# hacker-house-esp32-board.net
KiCad netlist of a schematic drawn in EAGLE
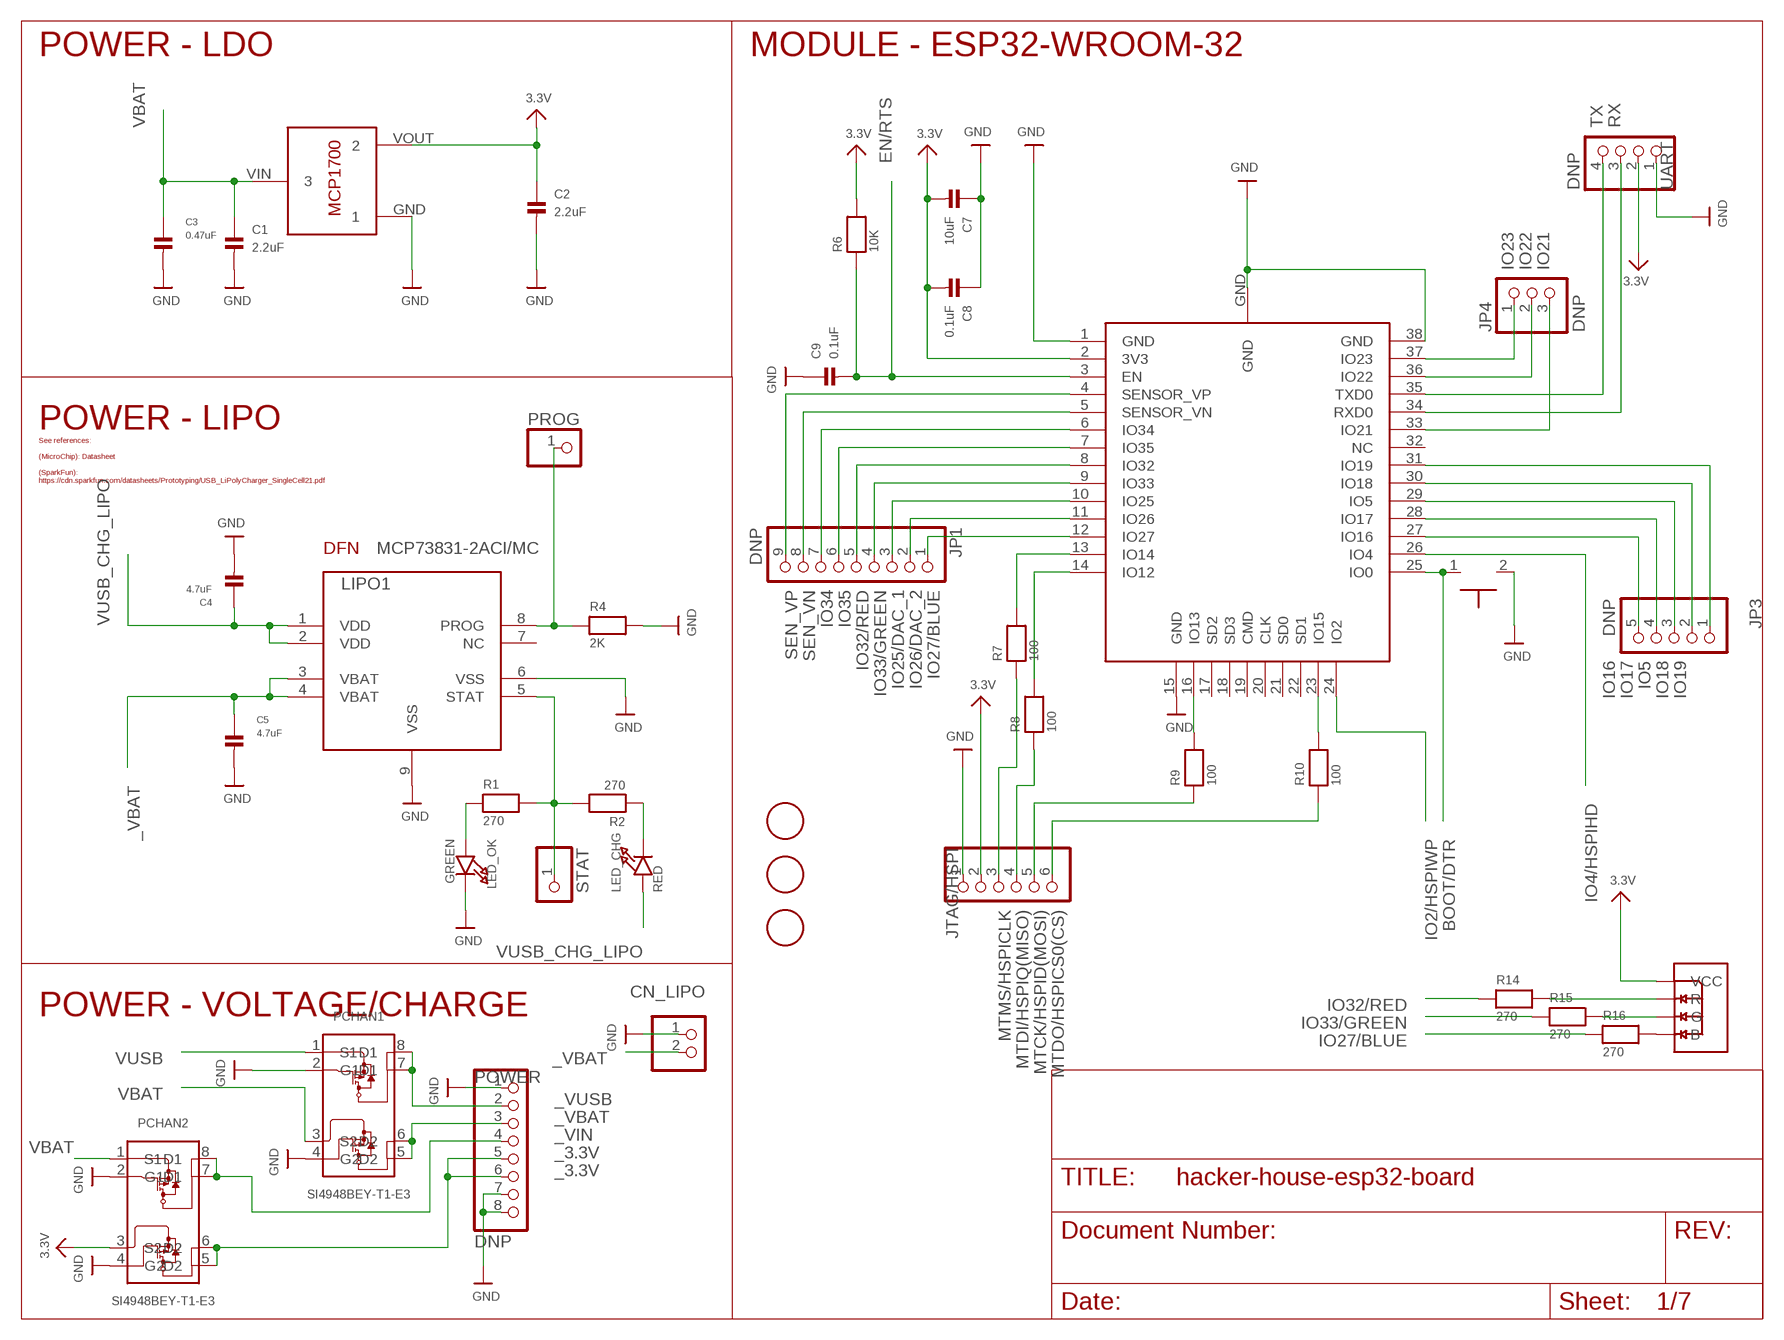
[diagram p0: schematic, sheet 1]
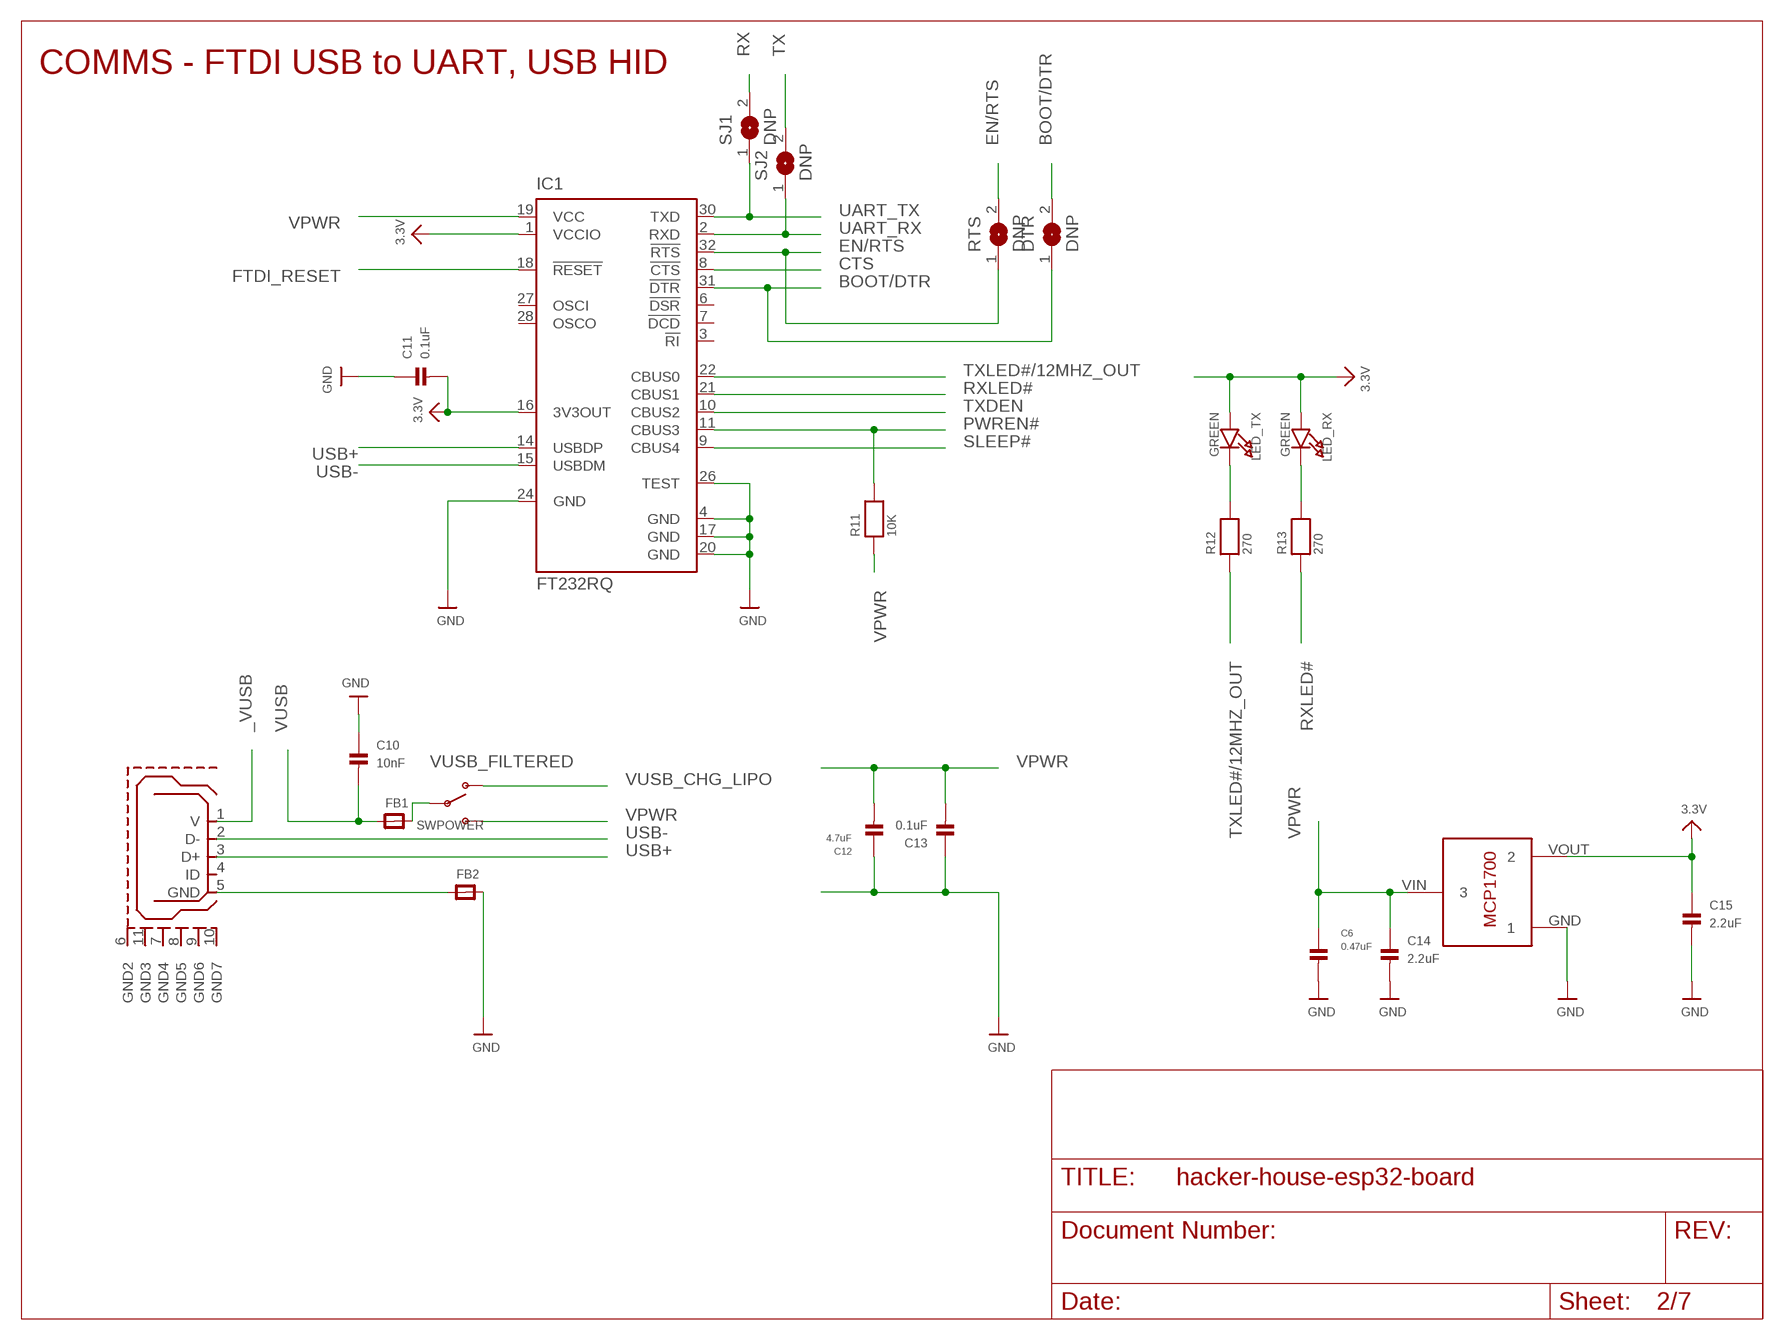
[diagram p1: schematic, sheet 2]
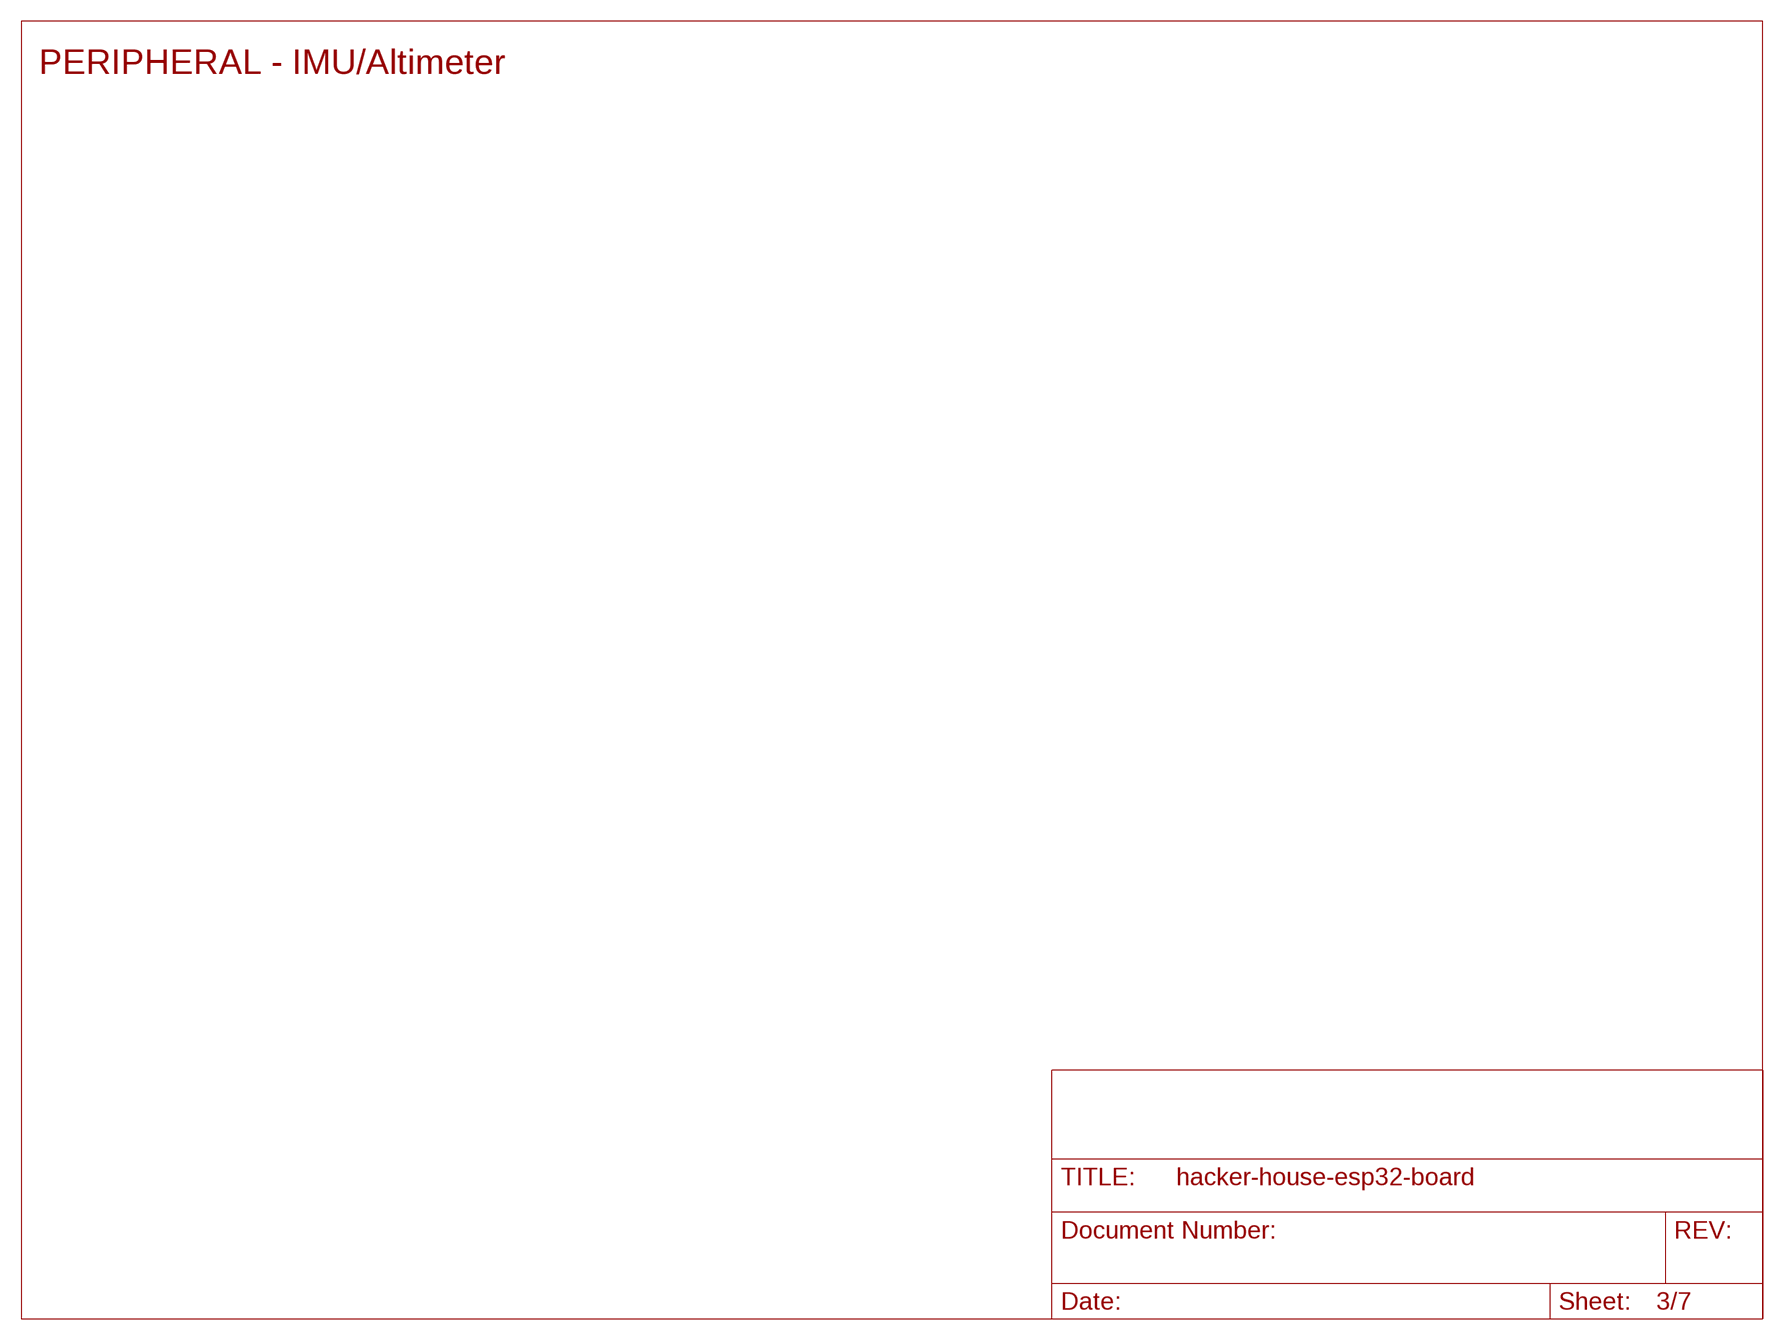
[diagram p2: schematic, sheet 3]
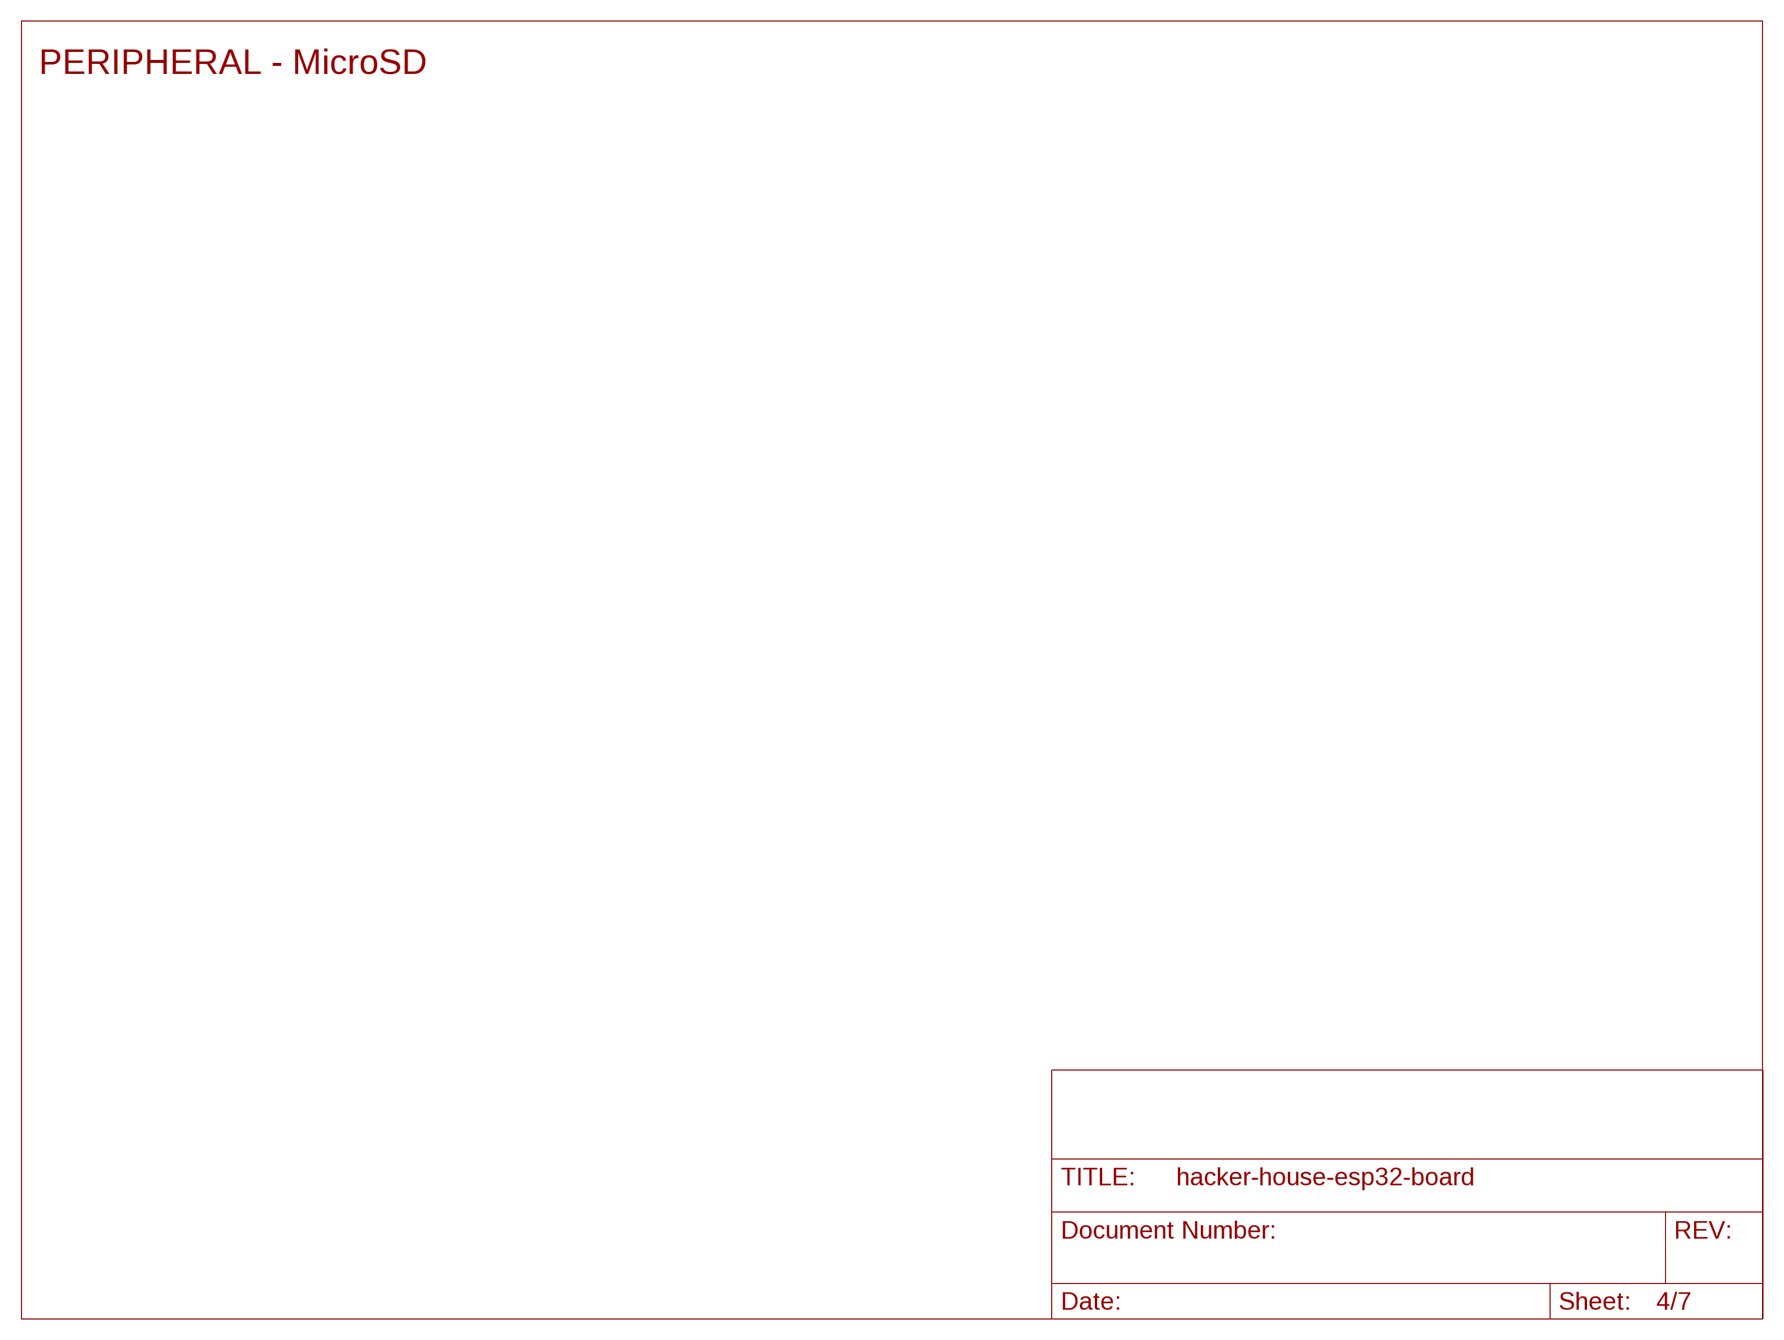
[diagram p3: schematic, sheet 4]
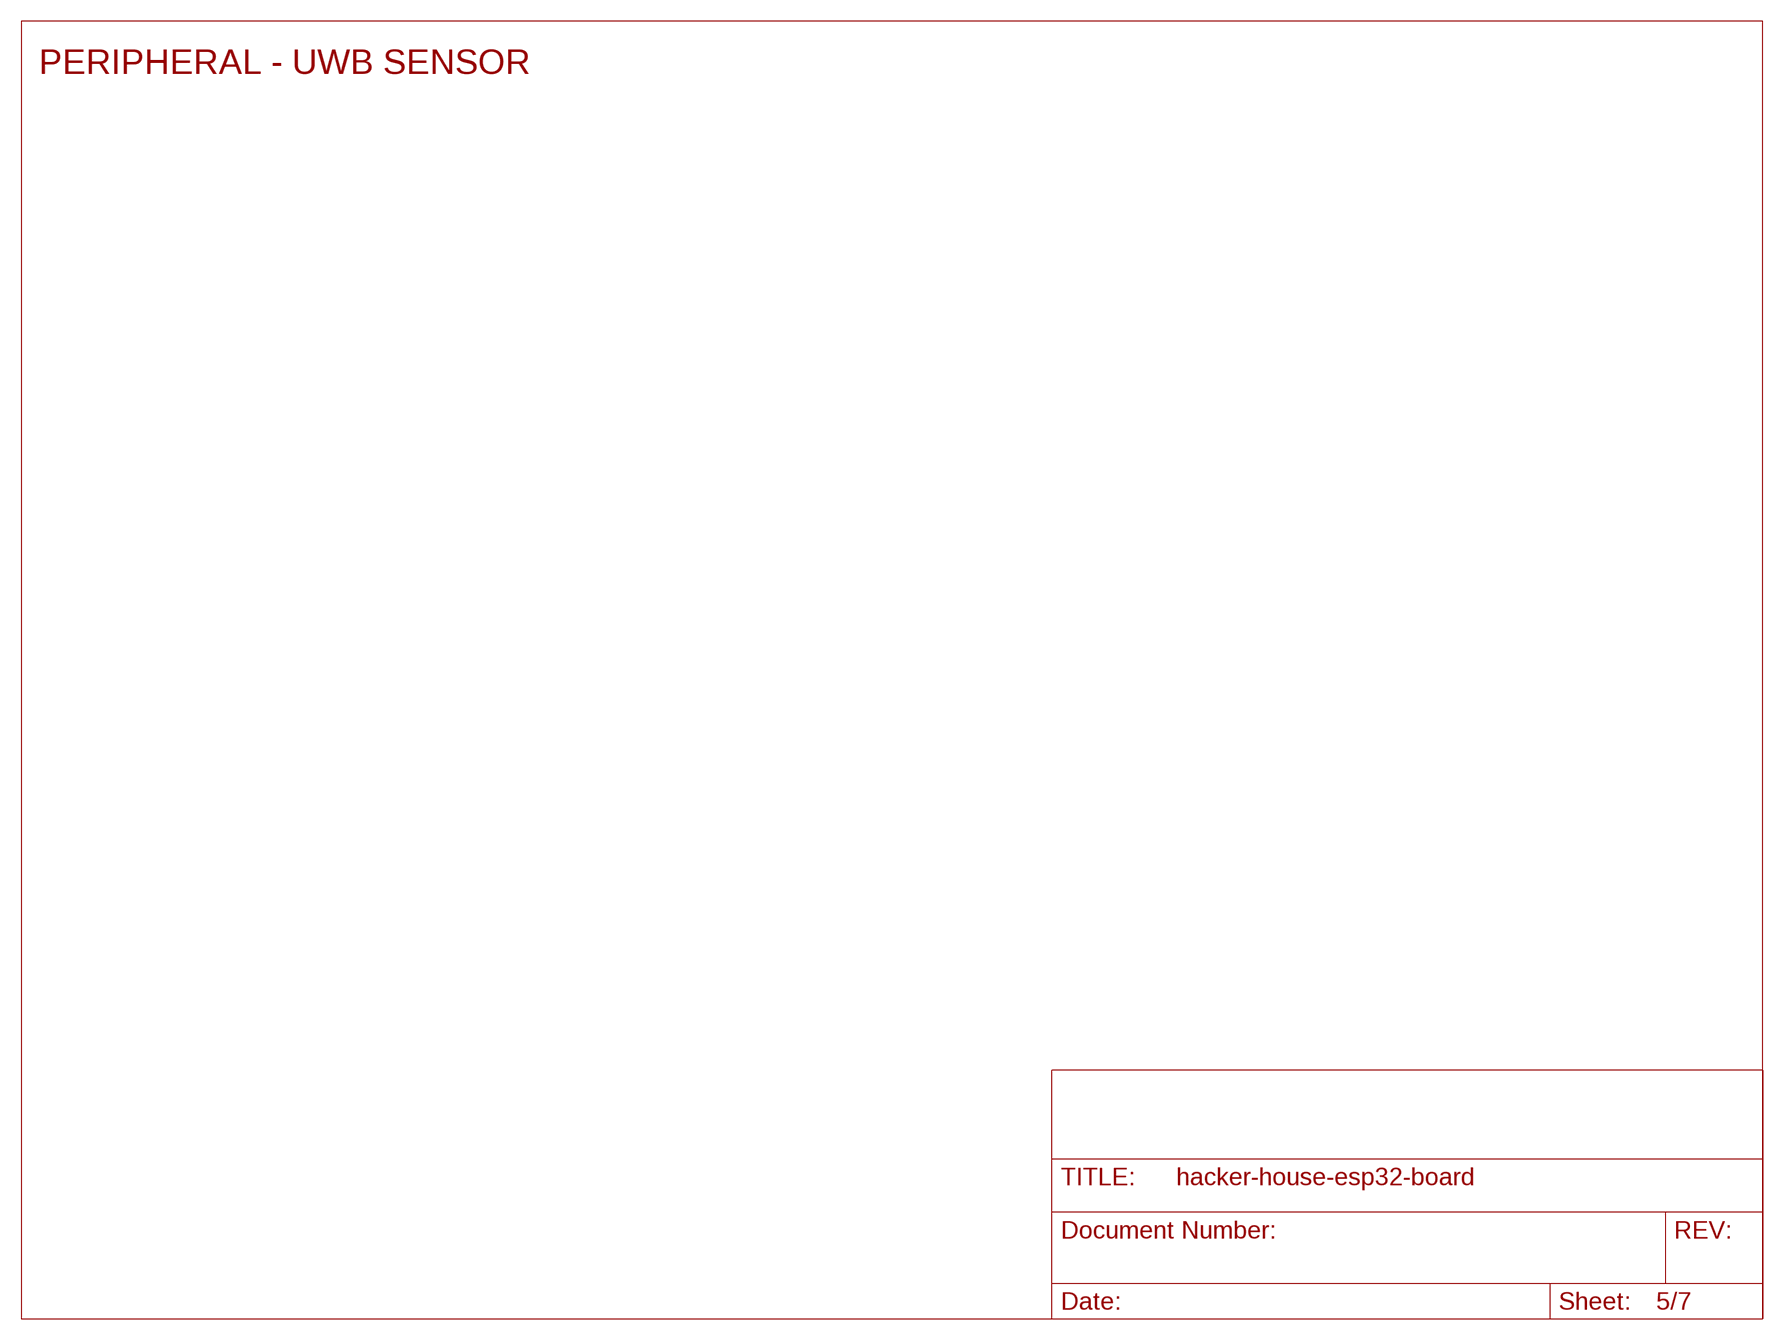
[diagram p4: schematic, sheet 5]
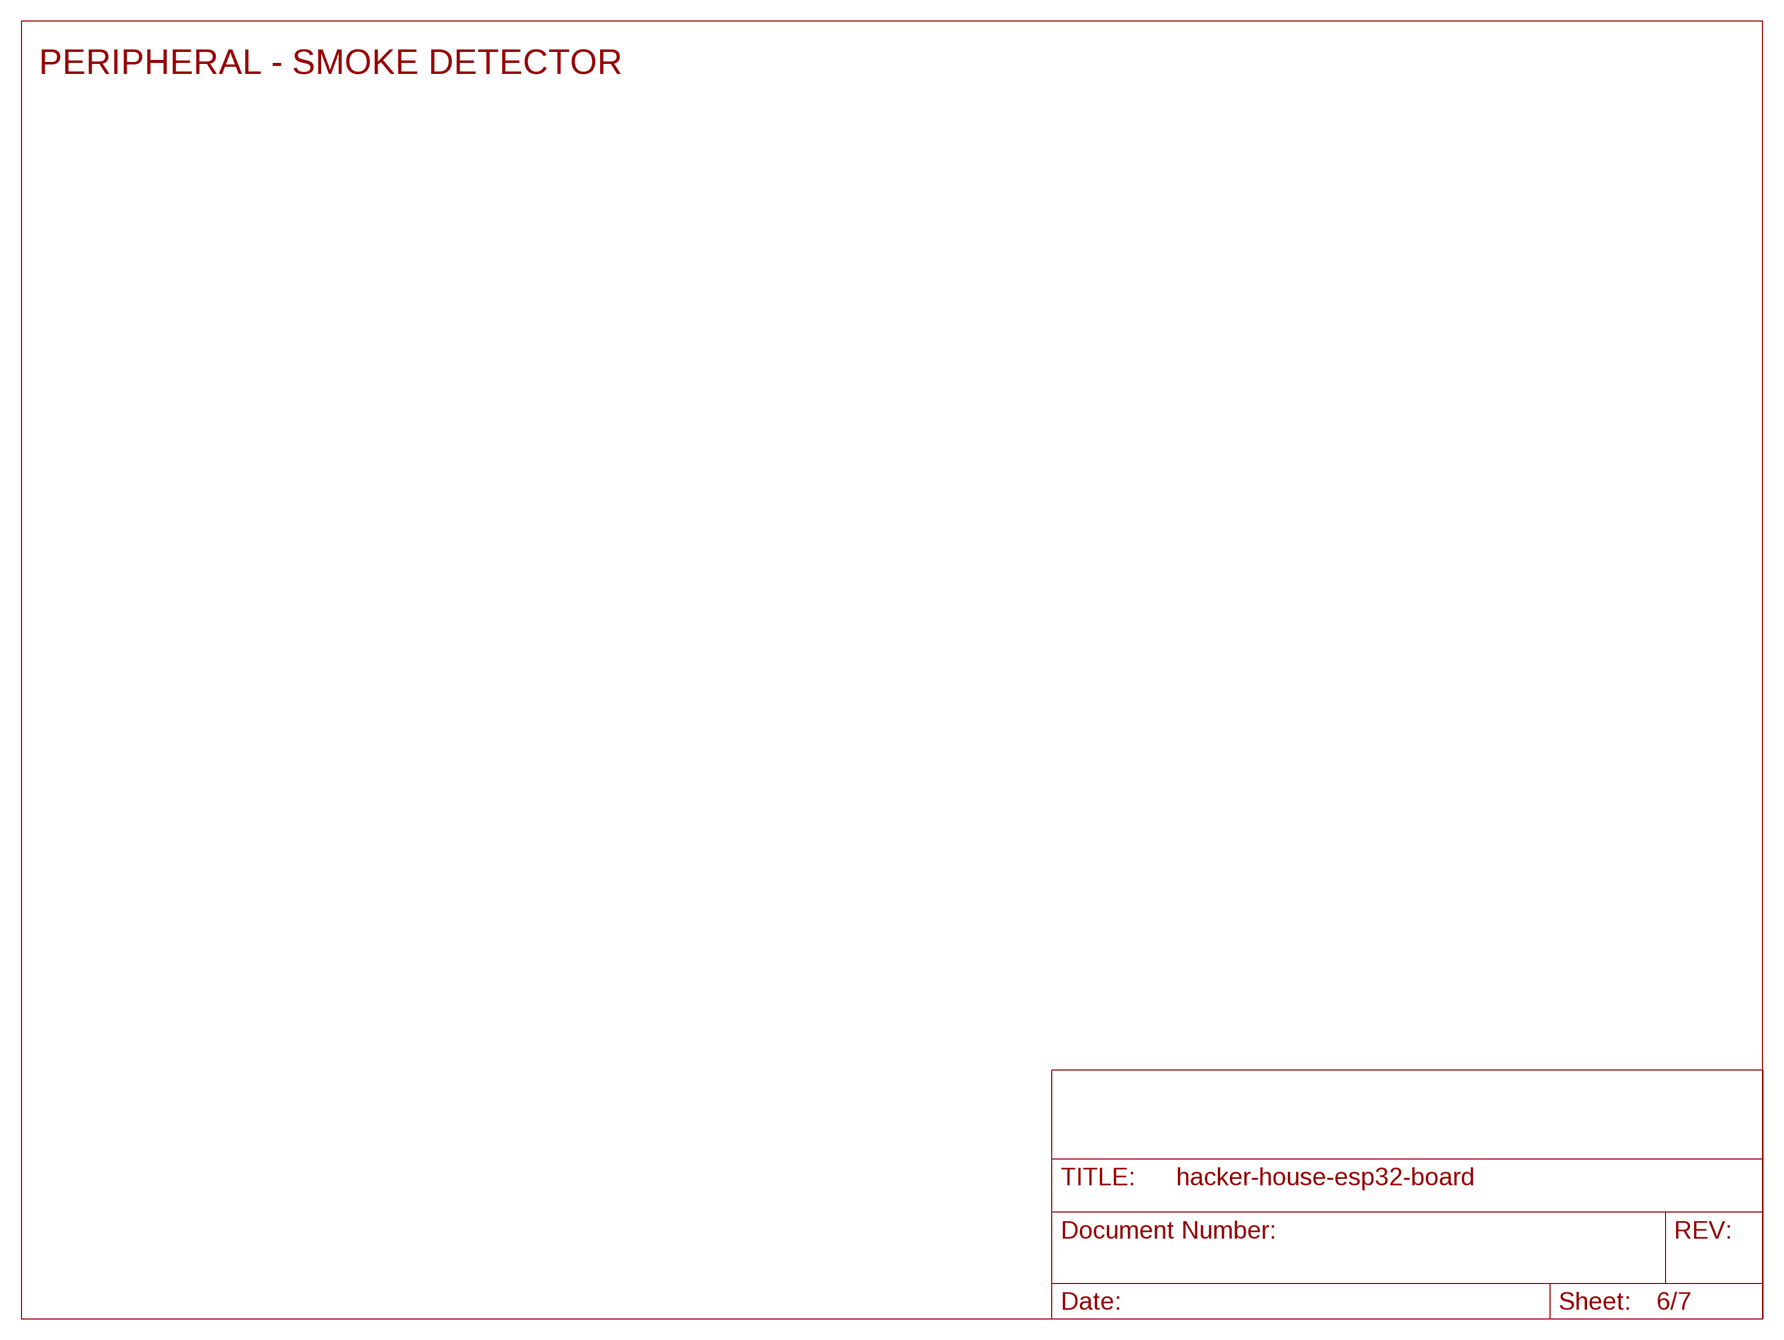
[diagram p5: schematic, sheet 6]
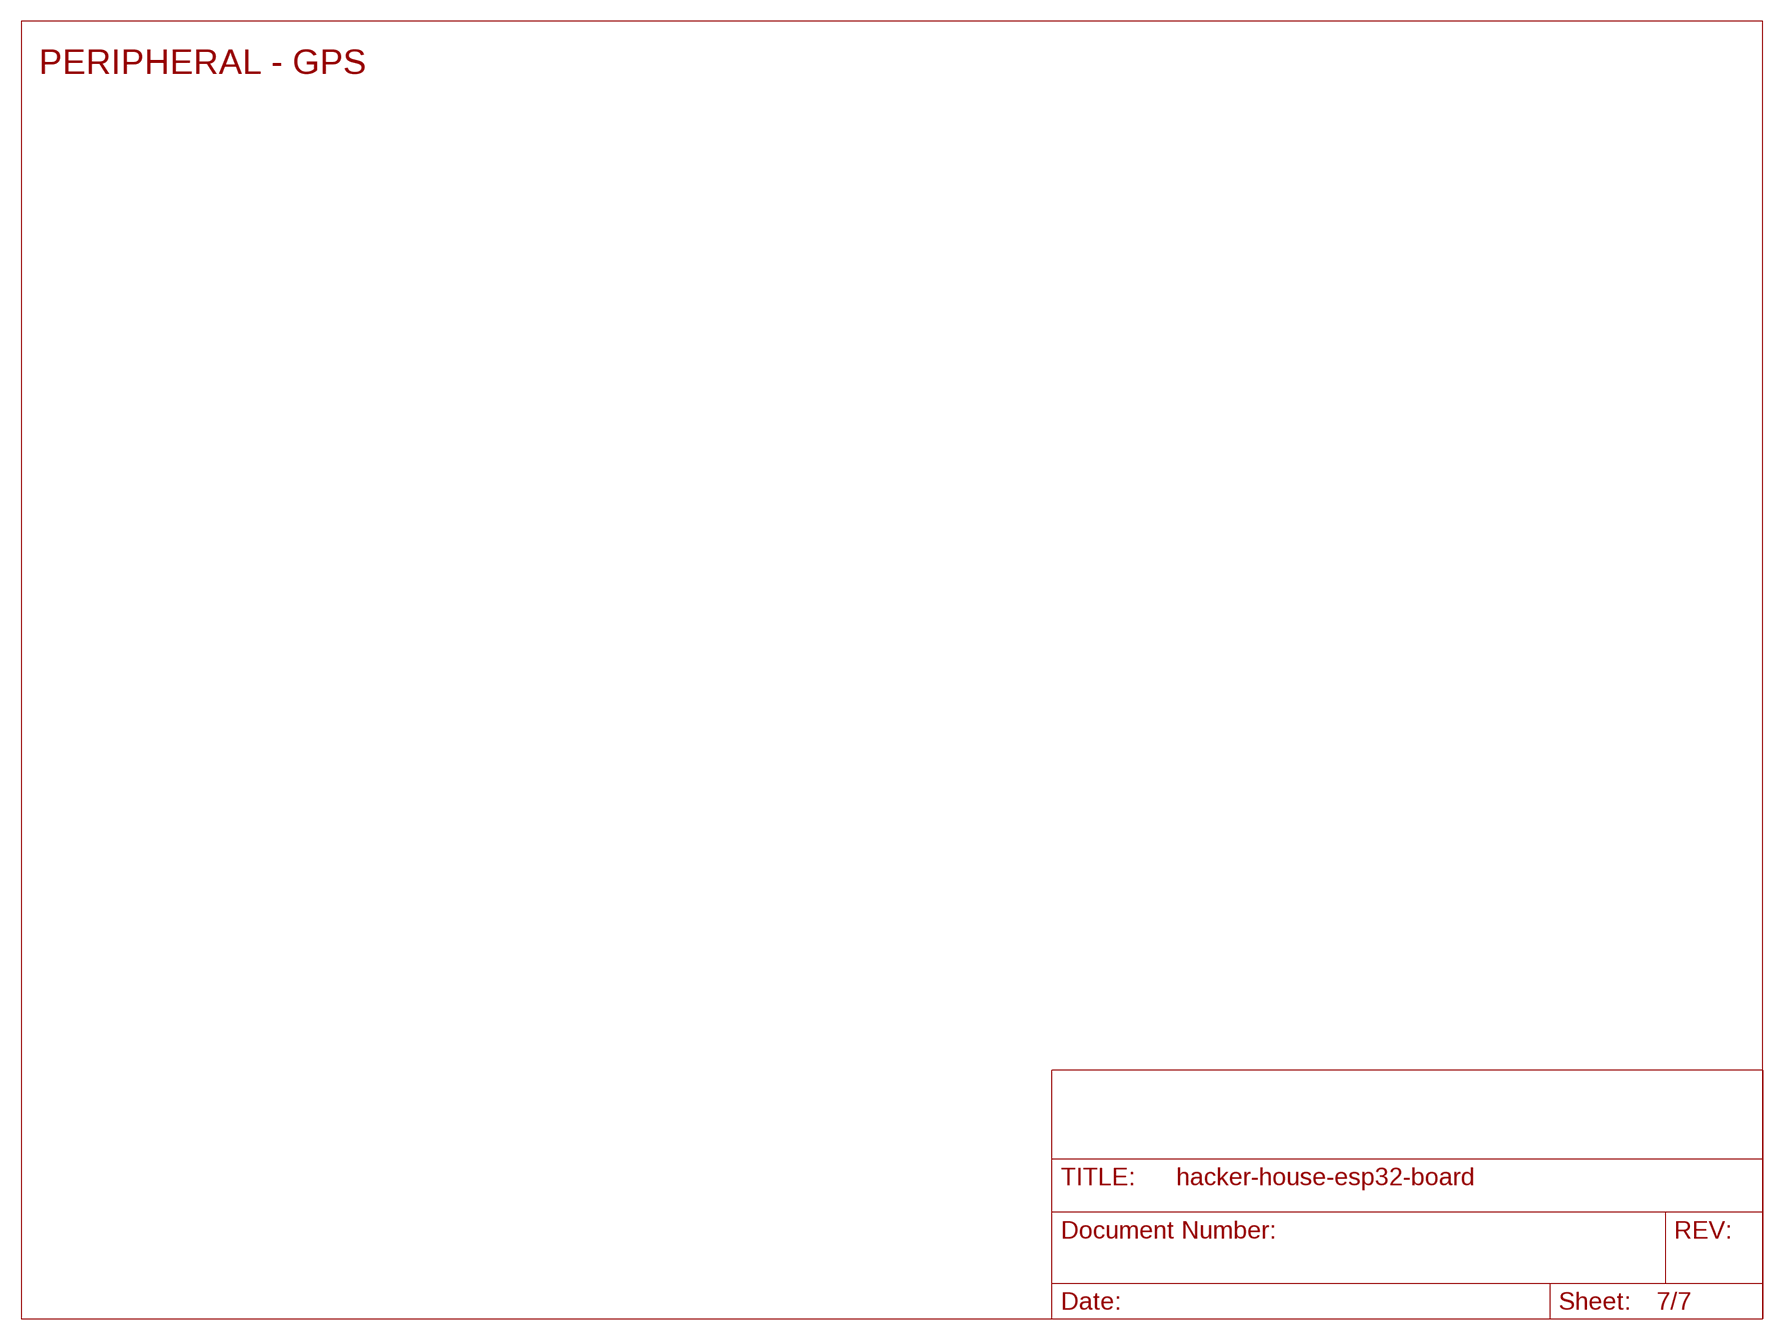
[diagram p6: schematic, sheet 7]

(export (version "E")
  (design (tool "Eeschema 10.0.6"))
  (components
    (comp (ref "C6")
      (value "0.47uF")
      (footprint "eagle-import:_0402MP")
      (fields (field (name "MPN") "GRM155R60J474KE19D"))
      (libsource (lib "eagle-import") (part "CAP_CERAMIC_0402MP"))
    )
    (comp (ref "C10")
      (value "10nF")
      (footprint "eagle-import:_0402MP")
      (fields (field (name "MPN") "GRM155R71E103KA01D"))
      (libsource (lib "eagle-import") (part "CAP_CERAMIC_0402MP"))
    )
    (comp (ref "C11")
      (value "0.1uF")
      (footprint "eagle-import:_0402MP")
      (fields (field (name "MPN") "CC0402KRX7R6BB104"))
      (libsource (lib "eagle-import") (part "CAP_CERAMIC_0402MP"))
    )
    (comp (ref "C12")
      (value "4.7uF")
      (footprint "eagle-import:_0402MP")
      (fields (field (name "MPN") "GRM155R60G475ME47D"))
      (libsource (lib "eagle-import") (part "CAP_CERAMIC_0402MP"))
    )
    (comp (ref "C13")
      (value "0.1uF")
      (footprint "eagle-import:_0402MP")
      (fields (field (name "MPN") "CC0402KRX7R6BB104"))
      (libsource (lib "eagle-import") (part "CAP_CERAMIC_0402MP"))
    )
    (comp (ref "C14")
      (value "2.2uF")
      (footprint "eagle-import:_0402MP")
      (fields (field (name "MPN") "C1005X5R0J225K050BC"))
      (libsource (lib "eagle-import") (part "CAP_CERAMIC_0402MP"))
    )
    (comp (ref "C15")
      (value "2.2uF")
      (footprint "eagle-import:_0402MP")
      (fields (field (name "MPN") "C1005X5R0J225K050BC"))
      (libsource (lib "eagle-import") (part "CAP_CERAMIC_0402MP"))
    )
    (comp (ref "DTR")
      (value "DNP")
      (footprint "eagle-import:SOLDERJUMPER_CLOSEDWIRE")
      (libsource (lib "eagle-import") (part "SOLDERJUMPERCLOSED"))
    )
    (comp (ref "FB1")
      (value "FERRITE_0603MP")
      (footprint "eagle-import:_0603MP")
      (fields (field (name "MPN") "BLM18RK102SN1D"))
      (libsource (lib "eagle-import") (part "FERRITE_0603MP"))
    )
    (comp (ref "FB2")
      (value "FERRITE_0603MP")
      (footprint "eagle-import:_0603MP")
      (fields (field (name "MPN") "BLM18RK102SN1D"))
      (libsource (lib "eagle-import") (part "FERRITE_0603MP"))
    )
    (comp (ref "IC1")
      (value "FT232RQ")
      (footprint "eagle-import:QFN32")
      (fields (field (name "MPN") "FT232RQ-REEL"))
      (libsource (lib "eagle-import") (part "FT232RQ"))
    )
    (comp (ref "LDO2")
      (value "3.3V")
      (footprint "eagle-import:MCP1700T-3302E_TT")
      (fields (field (name "MPN") "MCP1700T-3302E/TT"))
      (libsource (lib "eagle-import") (part "MCP1700T-3302E/TT"))
    )
    (comp (ref "LED_RX")
      (value "GREEN")
      (footprint "eagle-import:CHIPLED_0603_NOOUTLINE")
      (fields (field (name "MPN") "350-2035-1-ND"))
      (libsource (lib "eagle-import") (part "LED0603_NOOUTLINE"))
    )
    (comp (ref "LED_TX")
      (value "GREEN")
      (footprint "eagle-import:CHIPLED_0603_NOOUTLINE")
      (fields (field (name "MPN") "350-2035-1-ND"))
      (libsource (lib "eagle-import") (part "LED0603_NOOUTLINE"))
    )
    (comp (ref "R11")
      (value "10K")
      (footprint "eagle-import:_0402MP")
      (fields (field (name "MPN") "CRCW040210K0FKED"))
      (libsource (lib "eagle-import") (part "RESISTOR_0402MP"))
    )
    (comp (ref "R12")
      (value "270")
      (footprint "eagle-import:_0402MP")
      (fields (field (name "MPN") "CRCW0402270RFKED"))
      (libsource (lib "eagle-import") (part "RESISTOR_0402MP"))
    )
    (comp (ref "R13")
      (value "270")
      (footprint "eagle-import:_0402MP")
      (fields (field (name "MPN") "CRCW0402270RFKED"))
      (libsource (lib "eagle-import") (part "RESISTOR_0402MP"))
    )
    (comp (ref "RTS")
      (value "DNP")
      (footprint "eagle-import:SOLDERJUMPER_CLOSEDWIRE")
      (libsource (lib "eagle-import") (part "SOLDERJUMPERCLOSED"))
    )
    (comp (ref "SJ1")
      (value "DNP")
      (footprint "eagle-import:SOLDERJUMPER_CLOSEDWIRE")
      (libsource (lib "eagle-import") (part "SOLDERJUMPERCLOSED"))
    )
    (comp (ref "SJ2")
      (value "DNP")
      (footprint "eagle-import:SOLDERJUMPER_CLOSEDWIRE")
      (libsource (lib "eagle-import") (part "SOLDERJUMPERCLOSED"))
    )
    (comp (ref "SWPOWER")
      (value "SWITCH_SPDT")
      (footprint "eagle-import:SPDT_SMT_SSSS811101")
      (fields (field (name "MPN") "SSSS811101"))
      (libsource (lib "eagle-import") (part "SWITCH_SPDT"))
    )
    (comp (ref "U$14")
      (value "USB_MICROB")
      (footprint "eagle-import:USB_MICROB_PACKAGE")
      (fields (field (name "MPN") "ZX62-B-5PA(33)"))
      (libsource (lib "eagle-import") (part "USB_MICROB"))
    )
    (comp (ref "BOOT")
      (value "TACTILE_SWITCH_NO_GND_NO_BOSS")
      (footprint "eagle-import:SIDE_ACT_NO_GND_NO_BOSS")
      (fields (field (name "MPN") "B3U-3000P"))
      (libsource (lib "eagle-import") (part "TACTILE_SWITCH_NO_GND_NO_BOSS"))
    )
    (comp (ref "C1")
      (value "2.2uF")
      (footprint "eagle-import:_0402MP")
      (fields (field (name "MPN") "C1005X5R0J225K050BC"))
      (libsource (lib "eagle-import") (part "CAP_CERAMIC_0402MP"))
    )
    (comp (ref "C2")
      (value "2.2uF")
      (footprint "eagle-import:_0402MP")
      (fields (field (name "MPN") "C1005X5R0J225K050BC"))
      (libsource (lib "eagle-import") (part "CAP_CERAMIC_0402MP"))
    )
    (comp (ref "C3")
      (value "0.47uF")
      (footprint "eagle-import:_0402MP")
      (fields (field (name "MPN") "GRM155R60J474KE19D"))
      (libsource (lib "eagle-import") (part "CAP_CERAMIC_0402MP"))
    )
    (comp (ref "C4")
      (value "4.7uF")
      (footprint "eagle-import:_0402MP")
      (fields (field (name "MPN") "GRM155R60G475ME47D"))
      (libsource (lib "eagle-import") (part "CAP_CERAMIC_0402MP"))
    )
    (comp (ref "C5")
      (value "4.7uF")
      (footprint "eagle-import:_0402MP")
      (fields (field (name "MPN") "GRM155R60G475ME47D"))
      (libsource (lib "eagle-import") (part "CAP_CERAMIC_0402MP"))
    )
    (comp (ref "C7")
      (value "10uF")
      (footprint "eagle-import:_0603MP")
      (fields (field (name "MPN") "C1608X5R1A106K080AC"))
      (libsource (lib "eagle-import") (part "CAP_CERAMIC_0603MP"))
    )
    (comp (ref "C8")
      (value "0.1uF")
      (footprint "eagle-import:_0402MP")
      (fields (field (name "MPN") "CC0402KRX7R6BB104"))
      (libsource (lib "eagle-import") (part "CAP_CERAMIC_0402MP"))
    )
    (comp (ref "C9")
      (value "0.1uF")
      (footprint "eagle-import:_0402MP")
      (fields (field (name "MPN") "CC0402KRX7R6BB104"))
      (libsource (lib "eagle-import") (part "CAP_CERAMIC_0402MP"))
    )
    (comp (ref "CN_LIPO")
      (value "JST_2PIN")
      (footprint "eagle-import:JSTPH2")
      (fields (field (name "MPN") "S2B-PH-SM4-TB(LF)(SN)"))
      (libsource (lib "eagle-import") (part "JST_2PIN"))
    )
    (comp (ref "FID1")
      (value "FIDUCIAL")
      (footprint "eagle-import:FIDUCIAL_1MM")
      (libsource (lib "eagle-import") (part "FIDUCIAL"))
    )
    (comp (ref "FID2")
      (value "FIDUCIAL")
      (footprint "eagle-import:FIDUCIAL_1MM")
      (libsource (lib "eagle-import") (part "FIDUCIAL"))
    )
    (comp (ref "FID3")
      (value "FIDUCIAL")
      (footprint "eagle-import:FIDUCIAL_1MM")
      (libsource (lib "eagle-import") (part "FIDUCIAL"))
    )
    (comp (ref "JP1")
      (value "DNP")
      (footprint "eagle-import:1X09")
      (libsource (lib "eagle-import") (part "PINHD-1X9"))
    )
    (comp (ref "JP3")
      (value "DNP")
      (footprint "eagle-import:1X05")
      (libsource (lib "eagle-import") (part "PINHD-1X5"))
    )
    (comp (ref "JP4")
      (value "DNP")
      (footprint "eagle-import:1X03")
      (libsource (lib "eagle-import") (part "PINHD-1X3"))
    )
    (comp (ref "JTAG/HSPI")
      (value "HEADER-1X6ROUND")
      (footprint "eagle-import:1X06_ROUND")
      (libsource (lib "eagle-import") (part "HEADER-1X6ROUND"))
    )
    (comp (ref "LDO1")
      (value "3.3V")
      (footprint "eagle-import:MCP1700T-3302E_TT")
      (fields (field (name "MPN") "MCP1700T-3302E/TT"))
      (libsource (lib "eagle-import") (part "MCP1700T-3302E/TT"))
    )
    (comp (ref "LED_CHG")
      (value "RED")
      (footprint "eagle-import:CHIPLED_0603_NOOUTLINE")
      (fields (field (name "MPN") "350-2029-1-ND"))
      (libsource (lib "eagle-import") (part "LED0603_NOOUTLINE"))
    )
    (comp (ref "LED_OK")
      (value "GREEN")
      (footprint "eagle-import:CHIPLED_0603_NOOUTLINE")
      (fields (field (name "MPN") "350-2035-1-ND"))
      (libsource (lib "eagle-import") (part "LED0603_NOOUTLINE"))
    )
    (comp (ref "LIPO1")
      (value "MCP73831-2ACI/MC")
      (footprint "eagle-import:2X3_DFN")
      (libsource (lib "eagle-import") (part "MCP73831-2ACI/MC"))
    )
    (comp (ref "MOD1")
      (value "ESP32-WROOM-32")
      (footprint "eagle-import:ESP32-WROOM-32-MODULE")
      (fields (field (name "MPN") "ESP32-WROOM-32D (16MB)"))
      (libsource (lib "eagle-import") (part "ESP32-WROOM-32"))
    )
    (comp (ref "PCHAN1")
      (value "SI4948BEY-T1-E3")
      (footprint "eagle-import:SO-8")
      (libsource (lib "eagle-import") (part "SI4948BEY-T1-E3"))
    )
    (comp (ref "PCHAN2")
      (value "SI4948BEY-T1-E3")
      (footprint "eagle-import:SO-8")
      (libsource (lib "eagle-import") (part "SI4948BEY-T1-E3"))
    )
    (comp (ref "POWER")
      (value "DNP")
      (footprint "eagle-import:1X08_OVAL")
      (libsource (lib "eagle-import") (part "HEADER-1X8"))
    )
    (comp (ref "PROG")
      (value "HEADER-1X1ROUND")
      (footprint "eagle-import:1X01_ROUND")
      (libsource (lib "eagle-import") (part "HEADER-1X1ROUND"))
    )
    (comp (ref "R1")
      (value "270")
      (footprint "eagle-import:_0402MP")
      (fields (field (name "MPN") "CRCW0402270RFKED"))
      (libsource (lib "eagle-import") (part "RESISTOR_0402MP"))
    )
    (comp (ref "R2")
      (value "270")
      (footprint "eagle-import:_0402MP")
      (fields (field (name "MPN") "CRCW0402270RFKED"))
      (libsource (lib "eagle-import") (part "RESISTOR_0402MP"))
    )
    (comp (ref "R4")
      (value "2K")
      (footprint "eagle-import:_0402MP")
      (fields (field (name "MPN") "CPF0402B2K0E1"))
      (libsource (lib "eagle-import") (part "RESISTOR_0402MP"))
    )
    (comp (ref "R6")
      (value "10K")
      (footprint "eagle-import:_0402MP")
      (fields (field (name "MPN") "CRCW040210K0FKED"))
      (libsource (lib "eagle-import") (part "RESISTOR_0402MP"))
    )
    (comp (ref "R7")
      (value "100")
      (footprint "eagle-import:_0402MP")
      (fields (field (name "MPN") "CPF0402B100RE1"))
      (libsource (lib "eagle-import") (part "RESISTOR_0402MP"))
    )
    (comp (ref "R8")
      (value "100")
      (footprint "eagle-import:_0402MP")
      (fields (field (name "MPN") "CPF0402B100RE1"))
      (libsource (lib "eagle-import") (part "RESISTOR_0402MP"))
    )
    (comp (ref "R9")
      (value "100")
      (footprint "eagle-import:_0402MP")
      (fields (field (name "MPN") "CPF0402B100RE1"))
      (libsource (lib "eagle-import") (part "RESISTOR_0402MP"))
    )
    (comp (ref "R10")
      (value "100")
      (footprint "eagle-import:_0402MP")
      (fields (field (name "MPN") "CPF0402B100RE1"))
      (libsource (lib "eagle-import") (part "RESISTOR_0402MP"))
    )
    (comp (ref "R14")
      (value "270")
      (footprint "eagle-import:_0402MP")
      (fields (field (name "MPN") "CRCW0402270RFKED"))
      (libsource (lib "eagle-import") (part "RESISTOR_0402MP"))
    )
    (comp (ref "R15")
      (value "270")
      (footprint "eagle-import:_0402MP")
      (fields (field (name "MPN") "CRCW0402270RFKED"))
      (libsource (lib "eagle-import") (part "RESISTOR_0402MP"))
    )
    (comp (ref "R16")
      (value "270")
      (footprint "eagle-import:_0402MP")
      (fields (field (name "MPN") "CRCW0402270RFKED"))
      (libsource (lib "eagle-import") (part "RESISTOR_0402MP"))
    )
    (comp (ref "RGB1")
      (value "LRTB_R48G")
      (footprint "eagle-import:LRTB_R48G")
      (fields (field (name "MPN") "LRTB R48G"))
      (libsource (lib "eagle-import") (part "LRTB_R48G"))
    )
    (comp (ref "STAT")
      (value "HEADER-1X1ROUND")
      (footprint "eagle-import:1X01_ROUND")
      (libsource (lib "eagle-import") (part "HEADER-1X1ROUND"))
    )
    (comp (ref "UART")
      (value "DNP")
      (footprint "eagle-import:1X04_ROUND")
      (libsource (lib "eagle-import") (part "HEADER-1X4ROUND"))
    )
  )
  (nets
    (net (code "1") (name "3.3V") (class "Default")
      (node (ref "C11") (pin "2") (pinfunction "P$2_2") (pintype "passive"))
      (node (ref "C15") (pin "1") (pinfunction "P$1_1") (pintype "passive"))
      (node (ref "C2") (pin "1") (pinfunction "P$1_1") (pintype "passive"))
      (node (ref "C7") (pin "2") (pinfunction "P$2_2") (pintype "passive"))
      (node (ref "C8") (pin "2") (pinfunction "P$2_2") (pintype "passive"))
      (node (ref "IC1") (pin "1") (pinfunction "VCCIO_1") (pintype "power_in"))
      (node (ref "IC1") (pin "16") (pinfunction "3V3OUT_16") (pintype "output"))
      (node (ref "JTAG/HSPI") (pin "2") (pinfunction "2_2") (pintype "passive"))
      (node (ref "LDO1") (pin "VOUT") (pinfunction "2_VOUT") (pintype "bidirectional"))
      (node (ref "LDO2") (pin "VOUT") (pinfunction "2_VOUT") (pintype "bidirectional"))
      (node (ref "LED_RX") (pin "A") (pinfunction "A_A") (pintype "passive"))
      (node (ref "LED_TX") (pin "A") (pinfunction "A_A") (pintype "passive"))
      (node (ref "MOD1") (pin "2") (pinfunction "3V3_2") (pintype "bidirectional"))
      (node (ref "PCHAN2") (pin "3") (pinfunction "S2_3") (pintype "bidirectional"))
      (node (ref "R6") (pin "2") (pinfunction "2_2") (pintype "passive"))
      (node (ref "RGB1") (pin "1") (pinfunction "VCC_1") (pintype "bidirectional"))
      (node (ref "UART") (pin "2") (pinfunction "2_2") (pintype "passive"))
    )
    (net (code "2") (name "BOOT{slash}DTR") (class "Default")
      (node (ref "BOOT") (pin "1") (pinfunction "1_1") (pintype "bidirectional"))
      (node (ref "DTR") (pin "1") (pinfunction "1_1") (pintype "passive"))
      (node (ref "DTR") (pin "2") (pinfunction "2_2") (pintype "passive"))
      (node (ref "IC1") (pin "31") (pinfunction "~{DTR}_31") (pintype "output"))
      (node (ref "MOD1") (pin "25") (pinfunction "IO0_25") (pintype "bidirectional"))
    )
    (net (code "3") (name "CTS") (class "Default")
      (node (ref "IC1") (pin "8") (pinfunction "~{CTS}_8") (pintype "input"))
    )
    (net (code "4") (name "EN{slash}RTS") (class "Default")
      (node (ref "C9") (pin "2") (pinfunction "P$2_2") (pintype "passive"))
      (node (ref "IC1") (pin "32") (pinfunction "~{RTS}_32") (pintype "output"))
      (node (ref "MOD1") (pin "3") (pinfunction "EN_3") (pintype "bidirectional"))
      (node (ref "R6") (pin "1") (pinfunction "1_1") (pintype "passive"))
      (node (ref "RTS") (pin "1") (pinfunction "1_1") (pintype "passive"))
      (node (ref "RTS") (pin "2") (pinfunction "2_2") (pintype "passive"))
    )
    (net (code "5") (name "FTDI_RESET") (class "Default")
      (node (ref "IC1") (pin "18") (pinfunction "~{RESET}_18") (pintype "input"))
    )
    (net (code "6") (name "GND") (class "Default")
      (node (ref "BOOT") (pin "2") (pinfunction "2_2") (pintype "bidirectional"))
      (node (ref "C1") (pin "2") (pinfunction "P$2_2") (pintype "passive"))
      (node (ref "C10") (pin "1") (pinfunction "P$1_1") (pintype "passive"))
      (node (ref "C11") (pin "1") (pinfunction "P$1_1") (pintype "passive"))
      (node (ref "C12") (pin "1") (pinfunction "P$1_1") (pintype "passive"))
      (node (ref "C13") (pin "1") (pinfunction "P$1_1") (pintype "passive"))
      (node (ref "C14") (pin "2") (pinfunction "P$2_2") (pintype "passive"))
      (node (ref "C15") (pin "2") (pinfunction "P$2_2") (pintype "passive"))
      (node (ref "C2") (pin "2") (pinfunction "P$2_2") (pintype "passive"))
      (node (ref "C3") (pin "2") (pinfunction "P$2_2") (pintype "passive"))
      (node (ref "C4") (pin "2") (pinfunction "P$2_2") (pintype "passive"))
      (node (ref "C5") (pin "2") (pinfunction "P$2_2") (pintype "passive"))
      (node (ref "C6") (pin "2") (pinfunction "P$2_2") (pintype "passive"))
      (node (ref "C7") (pin "1") (pinfunction "P$1_1") (pintype "passive"))
      (node (ref "C8") (pin "1") (pinfunction "P$1_1") (pintype "passive"))
      (node (ref "C9") (pin "1") (pinfunction "P$1_1") (pintype "passive"))
      (node (ref "CN_LIPO") (pin "1") (pinfunction "1_1") (pintype "passive"))
      (node (ref "FB2") (pin "2") (pinfunction "P$2_2") (pintype "passive"))
      (node (ref "IC1") (pin "17") (pinfunction "GND_17") (pintype "power_in"))
      (node (ref "IC1") (pin "20") (pinfunction "GND_20") (pintype "power_in"))
      (node (ref "IC1") (pin "24") (pinfunction "GND_24") (pintype "power_in"))
      (node (ref "IC1") (pin "26") (pinfunction "TEST_26") (pintype "input"))
      (node (ref "IC1") (pin "4") (pinfunction "GND_4") (pintype "power_in"))
      (node (ref "JTAG/HSPI") (pin "1") (pinfunction "1_1") (pintype "passive"))
      (node (ref "LDO1") (pin "GND") (pinfunction "1_GND") (pintype "bidirectional"))
      (node (ref "LDO2") (pin "GND") (pinfunction "1_GND") (pintype "bidirectional"))
      (node (ref "LED_OK") (pin "C") (pinfunction "C_C") (pintype "passive"))
      (node (ref "LIPO1") (pin "6") (pinfunction "VSS_6") (pintype "bidirectional"))
      (node (ref "LIPO1") (pin "9") (pinfunction "VSS_9") (pintype "bidirectional"))
      (node (ref "MOD1") (pin "1") (pinfunction "GND_1") (pintype "bidirectional"))
      (node (ref "MOD1") (pin "15") (pinfunction "GND_15") (pintype "bidirectional"))
      (node (ref "MOD1") (pin "38") (pinfunction "GND_38") (pintype "bidirectional"))
      (node (ref "MOD1") (pin "GND") (pinfunction "GND_GND") (pintype "bidirectional"))
      (node (ref "PCHAN1") (pin "2") (pinfunction "G1_2") (pintype "bidirectional"))
      (node (ref "PCHAN1") (pin "4") (pinfunction "G2_4") (pintype "bidirectional"))
      (node (ref "PCHAN2") (pin "2") (pinfunction "G1_2") (pintype "bidirectional"))
      (node (ref "PCHAN2") (pin "4") (pinfunction "G2_4") (pintype "bidirectional"))
      (node (ref "POWER") (pin "1") (pinfunction "1_1") (pintype "passive"))
      (node (ref "POWER") (pin "7") (pinfunction "7_7") (pintype "passive"))
      (node (ref "POWER") (pin "8") (pinfunction "8_8") (pintype "passive"))
      (node (ref "R4") (pin "2") (pinfunction "2_2") (pintype "passive"))
      (node (ref "UART") (pin "1") (pinfunction "1_1") (pintype "passive"))
    )
    (net (code "7") (name "IO2{slash}HSPIWP") (class "Default")
      (node (ref "MOD1") (pin "24") (pinfunction "IO2_24") (pintype "bidirectional"))
    )
    (net (code "8") (name "IO4{slash}HSPIHD") (class "Default")
      (node (ref "MOD1") (pin "26") (pinfunction "IO4_26") (pintype "bidirectional"))
    )
    (net (code "9") (name "IO5") (class "Default")
      (node (ref "JP3") (pin "3") (pinfunction "3_3") (pintype "passive"))
      (node (ref "MOD1") (pin "29") (pinfunction "IO5_29") (pintype "bidirectional"))
    )
    (net (code "10") (name "IO16") (class "Default")
      (node (ref "JP3") (pin "5") (pinfunction "5_5") (pintype "passive"))
      (node (ref "MOD1") (pin "27") (pinfunction "IO16_27") (pintype "bidirectional"))
    )
    (net (code "11") (name "IO17") (class "Default")
      (node (ref "JP3") (pin "4") (pinfunction "4_4") (pintype "passive"))
      (node (ref "MOD1") (pin "28") (pinfunction "IO17_28") (pintype "bidirectional"))
    )
    (net (code "12") (name "IO18") (class "Default")
      (node (ref "JP3") (pin "2") (pinfunction "2_2") (pintype "passive"))
      (node (ref "MOD1") (pin "30") (pinfunction "IO18_30") (pintype "bidirectional"))
    )
    (net (code "13") (name "IO19") (class "Default")
      (node (ref "JP3") (pin "1") (pinfunction "1_1") (pintype "passive"))
      (node (ref "MOD1") (pin "31") (pinfunction "IO19_31") (pintype "bidirectional"))
    )
    (net (code "14") (name "IO21") (class "Default")
      (node (ref "JP4") (pin "3") (pinfunction "3_3") (pintype "passive"))
      (node (ref "MOD1") (pin "33") (pinfunction "IO21_33") (pintype "bidirectional"))
    )
    (net (code "15") (name "IO22") (class "Default")
      (node (ref "JP4") (pin "2") (pinfunction "2_2") (pintype "passive"))
      (node (ref "MOD1") (pin "36") (pinfunction "IO22_36") (pintype "bidirectional"))
    )
    (net (code "16") (name "IO23") (class "Default")
      (node (ref "JP4") (pin "1") (pinfunction "1_1") (pintype "passive"))
      (node (ref "MOD1") (pin "37") (pinfunction "IO23_37") (pintype "bidirectional"))
    )
    (net (code "17") (name "IO25{slash}DAC_1") (class "Default")
      (node (ref "JP1") (pin "3") (pinfunction "3_3") (pintype "passive"))
      (node (ref "MOD1") (pin "10") (pinfunction "IO25_10") (pintype "bidirectional"))
    )
    (net (code "18") (name "IO26{slash}DAC_2") (class "Default")
      (node (ref "JP1") (pin "2") (pinfunction "2_2") (pintype "passive"))
      (node (ref "MOD1") (pin "11") (pinfunction "IO26_11") (pintype "bidirectional"))
    )
    (net (code "19") (name "IO27{slash}BLUE") (class "Default")
      (node (ref "JP1") (pin "1") (pinfunction "1_1") (pintype "passive"))
      (node (ref "MOD1") (pin "12") (pinfunction "IO27_12") (pintype "bidirectional"))
      (node (ref "R16") (pin "1") (pinfunction "1_1") (pintype "passive"))
    )
    (net (code "20") (name "IO32{slash}RED") (class "Default")
      (node (ref "JP1") (pin "5") (pinfunction "5_5") (pintype "passive"))
      (node (ref "MOD1") (pin "8") (pinfunction "IO32_8") (pintype "bidirectional"))
      (node (ref "R14") (pin "1") (pinfunction "1_1") (pintype "passive"))
    )
    (net (code "21") (name "IO33{slash}GREEN") (class "Default")
      (node (ref "JP1") (pin "4") (pinfunction "4_4") (pintype "passive"))
      (node (ref "MOD1") (pin "9") (pinfunction "IO33_9") (pintype "bidirectional"))
      (node (ref "R15") (pin "1") (pinfunction "1_1") (pintype "passive"))
    )
    (net (code "22") (name "IO34") (class "Default")
      (node (ref "JP1") (pin "7") (pinfunction "7_7") (pintype "passive"))
      (node (ref "MOD1") (pin "6") (pinfunction "IO34_6") (pintype "bidirectional"))
    )
    (net (code "23") (name "IO35") (class "Default")
      (node (ref "JP1") (pin "6") (pinfunction "6_6") (pintype "passive"))
      (node (ref "MOD1") (pin "7") (pinfunction "IO35_7") (pintype "bidirectional"))
    )
    (net (code "24") (name "MTCK{slash}HSPID(MOSI)") (class "Default")
      (node (ref "JTAG/HSPI") (pin "5") (pinfunction "5_5") (pintype "passive"))
      (node (ref "R9") (pin "1") (pinfunction "1_1") (pintype "passive"))
    )
    (net (code "25") (name "MTDI{slash}HSPIQ(MISO)") (class "Default")
      (node (ref "JTAG/HSPI") (pin "4") (pinfunction "4_4") (pintype "passive"))
      (node (ref "R8") (pin "1") (pinfunction "1_1") (pintype "passive"))
    )
    (net (code "26") (name "MTDO{slash}HSPICS0(CS)") (class "Default")
      (node (ref "JTAG/HSPI") (pin "6") (pinfunction "6_6") (pintype "passive"))
      (node (ref "R10") (pin "1") (pinfunction "1_1") (pintype "passive"))
    )
    (net (code "27") (name "MTMS{slash}HSPICLK") (class "Default")
      (node (ref "JTAG/HSPI") (pin "3") (pinfunction "3_3") (pintype "passive"))
      (node (ref "R7") (pin "1") (pinfunction "1_1") (pintype "passive"))
    )
    (net (code "28") (name "Net-(FB2-P$1)") (class "Default")
      (node (ref "FB2") (pin "1") (pinfunction "P$1_1") (pintype "passive"))
      (node (ref "U$14") (pin "5") (pinfunction "GND_5") (pintype "bidirectional"))
    )
    (net (code "29") (name "Net-(LED_CHG-PadC)") (class "Default")
      (node (ref "LED_CHG") (pin "C") (pinfunction "C_C") (pintype "passive"))
      (node (ref "R2") (pin "1") (pinfunction "1_1") (pintype "passive"))
    )
    (net (code "30") (name "Net-(LED_OK-PadA)") (class "Default")
      (node (ref "LED_OK") (pin "A") (pinfunction "A_A") (pintype "passive"))
      (node (ref "R1") (pin "1") (pinfunction "1_1") (pintype "passive"))
    )
    (net (code "31") (name "Net-(LED_RX-PadC)") (class "Default")
      (node (ref "LED_RX") (pin "C") (pinfunction "C_C") (pintype "passive"))
      (node (ref "R13") (pin "2") (pinfunction "2_2") (pintype "passive"))
    )
    (net (code "32") (name "Net-(LED_TX-PadC)") (class "Default")
      (node (ref "LED_TX") (pin "C") (pinfunction "C_C") (pintype "passive"))
      (node (ref "R12") (pin "2") (pinfunction "2_2") (pintype "passive"))
    )
    (net (code "33") (name "Net-(LIPO1-PROG)") (class "Default")
      (node (ref "LIPO1") (pin "8") (pinfunction "PROG_8") (pintype "bidirectional"))
      (node (ref "PROG") (pin "1") (pinfunction "1_1") (pintype "passive"))
      (node (ref "R4") (pin "1") (pinfunction "1_1") (pintype "passive"))
    )
    (net (code "34") (name "Net-(LIPO1-STAT)") (class "Default")
      (node (ref "LIPO1") (pin "5") (pinfunction "STAT_5") (pintype "bidirectional"))
      (node (ref "R1") (pin "2") (pinfunction "2_2") (pintype "passive"))
      (node (ref "R2") (pin "2") (pinfunction "2_2") (pintype "passive"))
      (node (ref "STAT") (pin "1") (pinfunction "1_1") (pintype "passive"))
    )
    (net (code "35") (name "Net-(MOD1-IO12)") (class "Default")
      (node (ref "MOD1") (pin "14") (pinfunction "IO12_14") (pintype "bidirectional"))
      (node (ref "R8") (pin "2") (pinfunction "2_2") (pintype "passive"))
    )
    (net (code "36") (name "Net-(MOD1-IO13)") (class "Default")
      (node (ref "MOD1") (pin "16") (pinfunction "IO13_16") (pintype "bidirectional"))
      (node (ref "R9") (pin "2") (pinfunction "2_2") (pintype "passive"))
    )
    (net (code "37") (name "Net-(MOD1-IO14)") (class "Default")
      (node (ref "MOD1") (pin "13") (pinfunction "IO14_13") (pintype "bidirectional"))
      (node (ref "R7") (pin "2") (pinfunction "2_2") (pintype "passive"))
    )
    (net (code "38") (name "Net-(MOD1-IO15)") (class "Default")
      (node (ref "MOD1") (pin "23") (pinfunction "IO15_23") (pintype "bidirectional"))
      (node (ref "R10") (pin "2") (pinfunction "2_2") (pintype "passive"))
    )
    (net (code "39") (name "Net-(RGB1-B)") (class "Default")
      (node (ref "R16") (pin "2") (pinfunction "2_2") (pintype "passive"))
      (node (ref "RGB1") (pin "4") (pinfunction "B_4") (pintype "bidirectional"))
    )
    (net (code "40") (name "Net-(RGB1-G)") (class "Default")
      (node (ref "R15") (pin "2") (pinfunction "2_2") (pintype "passive"))
      (node (ref "RGB1") (pin "3") (pinfunction "G_3") (pintype "bidirectional"))
    )
    (net (code "41") (name "Net-(RGB1-R)") (class "Default")
      (node (ref "R14") (pin "2") (pinfunction "2_2") (pintype "passive"))
      (node (ref "RGB1") (pin "2") (pinfunction "R_2") (pintype "bidirectional"))
    )
    (net (code "42") (name "PWREN#") (class "Default")
      (node (ref "IC1") (pin "11") (pinfunction "CBUS3_11") (pintype "bidirectional"))
      (node (ref "R11") (pin "2") (pinfunction "2_2") (pintype "passive"))
    )
    (net (code "43") (name "RX") (class "Default")
      (node (ref "MOD1") (pin "34") (pinfunction "RXD0_34") (pintype "bidirectional"))
      (node (ref "SJ1") (pin "2") (pinfunction "2_2") (pintype "passive"))
      (node (ref "UART") (pin "3") (pinfunction "3_3") (pintype "passive"))
    )
    (net (code "44") (name "RXLED#") (class "Default")
      (node (ref "IC1") (pin "21") (pinfunction "CBUS1_21") (pintype "bidirectional"))
      (node (ref "R13") (pin "1") (pinfunction "1_1") (pintype "passive"))
    )
    (net (code "45") (name "SEN_VN") (class "Default")
      (node (ref "JP1") (pin "8") (pinfunction "8_8") (pintype "passive"))
      (node (ref "MOD1") (pin "5") (pinfunction "SENSOR_VN_5") (pintype "bidirectional"))
    )
    (net (code "46") (name "SEN_VP") (class "Default")
      (node (ref "JP1") (pin "9") (pinfunction "9_9") (pintype "passive"))
      (node (ref "MOD1") (pin "4") (pinfunction "SENSOR_VP_4") (pintype "bidirectional"))
    )
    (net (code "47") (name "SLEEP#") (class "Default")
      (node (ref "IC1") (pin "9") (pinfunction "CBUS4_9") (pintype "bidirectional"))
    )
    (net (code "48") (name "TX") (class "Default")
      (node (ref "MOD1") (pin "35") (pinfunction "TXD0_35") (pintype "bidirectional"))
      (node (ref "SJ2") (pin "2") (pinfunction "2_2") (pintype "passive"))
      (node (ref "UART") (pin "4") (pinfunction "4_4") (pintype "passive"))
    )
    (net (code "49") (name "TXDEN") (class "Default")
      (node (ref "IC1") (pin "10") (pinfunction "CBUS2_10") (pintype "bidirectional"))
    )
    (net (code "50") (name "TXLED#{slash}12MHZ_OUT") (class "Default")
      (node (ref "IC1") (pin "22") (pinfunction "CBUS0_22") (pintype "bidirectional"))
      (node (ref "R12") (pin "1") (pinfunction "1_1") (pintype "passive"))
    )
    (net (code "51") (name "UART_RX") (class "Default")
      (node (ref "IC1") (pin "2") (pinfunction "RXD_2") (pintype "input"))
      (node (ref "SJ2") (pin "1") (pinfunction "1_1") (pintype "passive"))
    )
    (net (code "52") (name "UART_TX") (class "Default")
      (node (ref "IC1") (pin "30") (pinfunction "TXD_30") (pintype "output"))
      (node (ref "SJ1") (pin "1") (pinfunction "1_1") (pintype "passive"))
    )
    (net (code "53") (name "USB+") (class "Default")
      (node (ref "IC1") (pin "14") (pinfunction "USBDP_14") (pintype "bidirectional"))
      (node (ref "U$14") (pin "3") (pinfunction "D+_3") (pintype "bidirectional"))
    )
    (net (code "54") (name "USB-") (class "Default")
      (node (ref "IC1") (pin "15") (pinfunction "USBDM_15") (pintype "bidirectional"))
      (node (ref "U$14") (pin "2") (pinfunction "D-_2") (pintype "bidirectional"))
    )
    (net (code "55") (name "VBAT") (class "Default")
      (node (ref "C1") (pin "1") (pinfunction "P$1_1") (pintype "passive"))
      (node (ref "C3") (pin "1") (pinfunction "P$1_1") (pintype "passive"))
      (node (ref "LDO1") (pin "VIN") (pinfunction "3_VIN") (pintype "bidirectional"))
      (node (ref "PCHAN1") (pin "3") (pinfunction "S2_3") (pintype "bidirectional"))
      (node (ref "PCHAN2") (pin "1") (pinfunction "S1_1") (pintype "bidirectional"))
    )
    (net (code "56") (name "VPWR") (class "Default")
      (node (ref "C12") (pin "2") (pinfunction "P$2_2") (pintype "passive"))
      (node (ref "C13") (pin "2") (pinfunction "P$2_2") (pintype "passive"))
      (node (ref "C14") (pin "1") (pinfunction "P$1_1") (pintype "passive"))
      (node (ref "C6") (pin "1") (pinfunction "P$1_1") (pintype "passive"))
      (node (ref "IC1") (pin "19") (pinfunction "VCC_19") (pintype "power_in"))
      (node (ref "LDO2") (pin "VIN") (pinfunction "3_VIN") (pintype "bidirectional"))
      (node (ref "R11") (pin "1") (pinfunction "1_1") (pintype "passive"))
      (node (ref "SWPOWER") (pin "C") (pinfunction "S_C") (pintype "passive"))
    )
    (net (code "57") (name "VUSB") (class "Default")
      (node (ref "C10") (pin "2") (pinfunction "P$2_2") (pintype "passive"))
      (node (ref "FB1") (pin "1") (pinfunction "P$1_1") (pintype "passive"))
      (node (ref "PCHAN1") (pin "1") (pinfunction "S1_1") (pintype "bidirectional"))
    )
    (net (code "58") (name "VUSB_CHG_LIPO") (class "Default")
      (node (ref "C4") (pin "1") (pinfunction "P$1_1") (pintype "passive"))
      (node (ref "LED_CHG") (pin "A") (pinfunction "A_A") (pintype "passive"))
      (node (ref "LIPO1") (pin "1") (pinfunction "VDD_1") (pintype "bidirectional"))
      (node (ref "LIPO1") (pin "2") (pinfunction "VDD_2") (pintype "bidirectional"))
      (node (ref "SWPOWER") (pin "A") (pinfunction "O_A") (pintype "passive"))
    )
    (net (code "59") (name "VUSB_FILTERED") (class "Default")
      (node (ref "FB1") (pin "2") (pinfunction "P$2_2") (pintype "passive"))
      (node (ref "SWPOWER") (pin "B") (pinfunction "P_B") (pintype "passive"))
    )
    (net (code "60") (name "_3.3V") (class "Default")
      (node (ref "PCHAN2") (pin "5") (pinfunction "D2_5") (pintype "bidirectional"))
      (node (ref "PCHAN2") (pin "6") (pinfunction "D2_6") (pintype "bidirectional"))
      (node (ref "POWER") (pin "5") (pinfunction "5_5") (pintype "passive"))
      (node (ref "POWER") (pin "6") (pinfunction "6_6") (pintype "passive"))
    )
    (net (code "61") (name "_VBAT") (class "Default")
      (node (ref "C5") (pin "1") (pinfunction "P$1_1") (pintype "passive"))
      (node (ref "CN_LIPO") (pin "2") (pinfunction "2_2") (pintype "passive"))
      (node (ref "LIPO1") (pin "3") (pinfunction "VBAT_3") (pintype "bidirectional"))
      (node (ref "LIPO1") (pin "4") (pinfunction "VBAT_4") (pintype "bidirectional"))
      (node (ref "PCHAN1") (pin "5") (pinfunction "D2_5") (pintype "bidirectional"))
      (node (ref "PCHAN1") (pin "6") (pinfunction "D2_6") (pintype "bidirectional"))
      (node (ref "POWER") (pin "3") (pinfunction "3_3") (pintype "passive"))
    )
    (net (code "62") (name "_VIN") (class "Default")
      (node (ref "PCHAN2") (pin "7") (pinfunction "D1_7") (pintype "bidirectional"))
      (node (ref "PCHAN2") (pin "8") (pinfunction "D1_8") (pintype "bidirectional"))
      (node (ref "POWER") (pin "4") (pinfunction "4_4") (pintype "passive"))
    )
    (net (code "63") (name "_VUSB") (class "Default")
      (node (ref "PCHAN1") (pin "7") (pinfunction "D1_7") (pintype "bidirectional"))
      (node (ref "PCHAN1") (pin "8") (pinfunction "D1_8") (pintype "bidirectional"))
      (node (ref "POWER") (pin "2") (pinfunction "2_2") (pintype "passive"))
      (node (ref "U$14") (pin "1") (pinfunction "V_1") (pintype "bidirectional"))
    )
    (net (code "64") (name "unconnected-(IC1-OSCI-Pad27)") (class "Default")
      (node (ref "IC1") (pin "27") (pinfunction "OSCI_27") (pintype "input"))
    )
    (net (code "65") (name "unconnected-(IC1-OSCO-Pad28)") (class "Default")
      (node (ref "IC1") (pin "28") (pinfunction "OSCO_28") (pintype "output"))
    )
    (net (code "66") (name "unconnected-(IC1-~{DCD}-Pad7)") (class "Default")
      (node (ref "IC1") (pin "7") (pinfunction "~{DCD}_7") (pintype "input"))
    )
    (net (code "67") (name "unconnected-(IC1-~{DSR}-Pad6)") (class "Default")
      (node (ref "IC1") (pin "6") (pinfunction "~{DSR}_6") (pintype "input"))
    )
    (net (code "68") (name "unconnected-(IC1-~{RI}-Pad3)") (class "Default")
      (node (ref "IC1") (pin "3") (pinfunction "~{RI}_3") (pintype "input"))
    )
    (net (code "69") (name "unconnected-(LIPO1-NC-Pad7)") (class "Default")
      (node (ref "LIPO1") (pin "7") (pinfunction "NC_7") (pintype "no_connect"))
    )
    (net (code "70") (name "unconnected-(MOD1-CLK-Pad20)") (class "Default")
      (node (ref "MOD1") (pin "20") (pinfunction "CLK_20") (pintype "bidirectional"))
    )
    (net (code "71") (name "unconnected-(MOD1-CMD-Pad19)") (class "Default")
      (node (ref "MOD1") (pin "19") (pinfunction "CMD_19") (pintype "bidirectional"))
    )
    (net (code "72") (name "unconnected-(MOD1-NC-Pad32)") (class "Default")
      (node (ref "MOD1") (pin "32") (pinfunction "NC_32") (pintype "no_connect"))
    )
    (net (code "73") (name "unconnected-(MOD1-SD0-Pad21)") (class "Default")
      (node (ref "MOD1") (pin "21") (pinfunction "SD0_21") (pintype "bidirectional"))
    )
    (net (code "74") (name "unconnected-(MOD1-SD1-Pad22)") (class "Default")
      (node (ref "MOD1") (pin "22") (pinfunction "SD1_22") (pintype "bidirectional"))
    )
    (net (code "75") (name "unconnected-(MOD1-SD2-Pad17)") (class "Default")
      (node (ref "MOD1") (pin "17") (pinfunction "SD2_17") (pintype "bidirectional"))
    )
    (net (code "76") (name "unconnected-(MOD1-SD3-Pad18)") (class "Default")
      (node (ref "MOD1") (pin "18") (pinfunction "SD3_18") (pintype "bidirectional"))
    )
    (net (code "77") (name "unconnected-(U$14-GND2-Pad6)") (class "Default")
      (node (ref "U$14") (pin "6") (pinfunction "GND2_6") (pintype "bidirectional"))
    )
    (net (code "78") (name "unconnected-(U$14-GND3-Pad11)") (class "Default")
      (node (ref "U$14") (pin "11") (pinfunction "GND3_11") (pintype "bidirectional"))
    )
    (net (code "79") (name "unconnected-(U$14-GND4-Pad7)") (class "Default")
      (node (ref "U$14") (pin "7") (pinfunction "GND4_7") (pintype "bidirectional"))
    )
    (net (code "80") (name "unconnected-(U$14-GND5-Pad8)") (class "Default")
      (node (ref "U$14") (pin "8") (pinfunction "GND5_8") (pintype "bidirectional"))
    )
    (net (code "81") (name "unconnected-(U$14-GND6-Pad9)") (class "Default")
      (node (ref "U$14") (pin "9") (pinfunction "GND6_9") (pintype "bidirectional"))
    )
    (net (code "82") (name "unconnected-(U$14-GND7-Pad10)") (class "Default")
      (node (ref "U$14") (pin "10") (pinfunction "GND7_10") (pintype "bidirectional"))
    )
    (net (code "83") (name "unconnected-(U$14-ID-Pad4)") (class "Default")
      (node (ref "U$14") (pin "4") (pinfunction "ID_4") (pintype "bidirectional"))
    )
  )
)
